# Ocreeb_MK_2__core__schematic.net
KiCad netlist of a schematic drawn in EAGLE
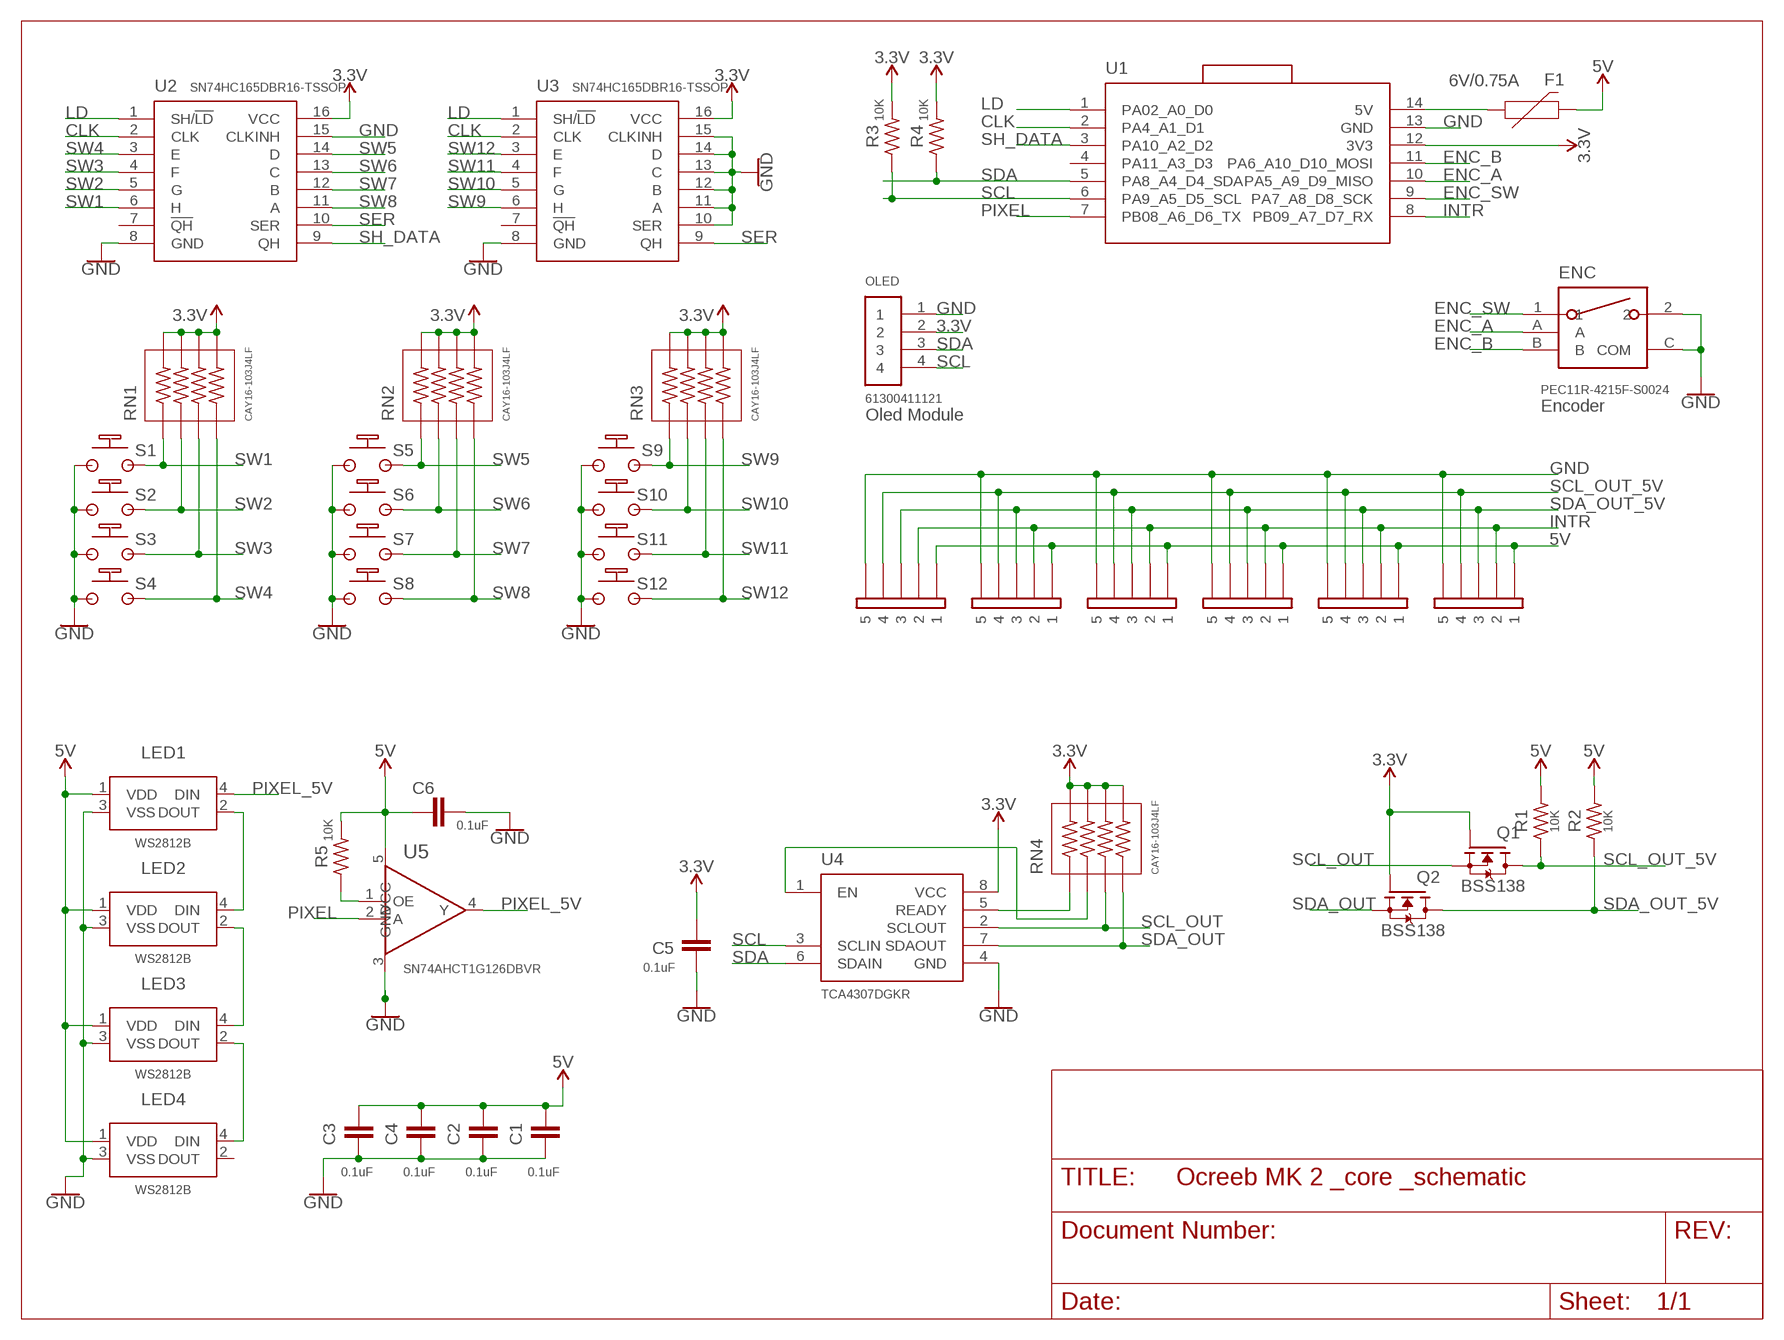
[diagram p0: schematic, sheet 1]

(export (version "E")
  (design (tool "Eeschema 10.0.6"))
  (components
    (comp (ref "C1")
      (value "0.1uF")
      (footprint "eagle-import:CAPC1608X85")
      (libsource (lib "eagle-import") (part "CCHIP-0603(1608-METRIC)_"))
    )
    (comp (ref "C2")
      (value "0.1uF")
      (footprint "eagle-import:CAPC1608X85")
      (libsource (lib "eagle-import") (part "CCHIP-0603(1608-METRIC)_"))
    )
    (comp (ref "C3")
      (value "0.1uF")
      (footprint "eagle-import:CAPC1608X85")
      (libsource (lib "eagle-import") (part "CCHIP-0603(1608-METRIC)_"))
    )
    (comp (ref "C4")
      (value "0.1uF")
      (footprint "eagle-import:CAPC1608X85")
      (libsource (lib "eagle-import") (part "CCHIP-0603(1608-METRIC)_"))
    )
    (comp (ref "C5")
      (value "0.1uF")
      (footprint "eagle-import:CAPC1608X85")
      (libsource (lib "eagle-import") (part "CCHIP-0603(1608-METRIC)_"))
    )
    (comp (ref "C6")
      (value "0.1uF")
      (footprint "eagle-import:CAPC1608X85")
      (libsource (lib "eagle-import") (part "CCHIP-0603(1608-METRIC)_"))
    )
    (comp (ref "ENC")
      (value "PEC11R-4215F-S0024")
      (footprint "eagle-import:PEC11R-4215F-S0024")
      (fields
        (field (name "DIGIKEY_PART_NUMBER") "PEC11R-4215F-S0024-ND")
        (field (name "MANUFACTURER") "Bourns Inc.")
        (field (name "CREATED_BY") "PCBLayout.com")
      )
      (libsource (lib "eagle-import") (part "PEC11R-4215F-S0024"))
    )
    (comp (ref "F1")
      (value "6V/0.75A")
      (footprint "eagle-import:1206")
      (libsource (lib "eagle-import") (part "PPTC_0.75A"))
    )
    (comp (ref "LED1")
      (value "WS2812B")
      (footprint "eagle-import:WS2812B")
      (fields (field (name "MANUFACTURER") "Worldsemi"))
      (libsource (lib "eagle-import") (part "WS2812B"))
    )
    (comp (ref "LED2")
      (value "WS2812B")
      (footprint "eagle-import:WS2812B")
      (fields (field (name "MANUFACTURER") "Worldsemi"))
      (libsource (lib "eagle-import") (part "WS2812B"))
    )
    (comp (ref "LED3")
      (value "WS2812B")
      (footprint "eagle-import:WS2812B")
      (fields (field (name "MANUFACTURER") "Worldsemi"))
      (libsource (lib "eagle-import") (part "WS2812B"))
    )
    (comp (ref "LED4")
      (value "WS2812B")
      (footprint "eagle-import:WS2812B")
      (fields (field (name "MANUFACTURER") "Worldsemi"))
      (libsource (lib "eagle-import") (part "WS2812B"))
    )
    (comp (ref "OLED")
      (value "61300411121")
      (footprint "eagle-import:61300411121")
      (fields
        (field (name "DIGI_KEY_PART_NUMBER") "732-5317-ND")
        (field (name "MANUFACTURER") "Wurth Electronics Inc.")
        (field (name "CREATED_BY") "PCBLayout.com")
      )
      (libsource (lib "eagle-import") (part "61300411121"))
    )
    (comp (ref "Q1")
      (value "BSS138")
      (footprint "eagle-import:SOT95P240X111-3N")
      (fields (field (name "MF") "onsemi"))
      (libsource (lib "eagle-import") (part "BSS138"))
    )
    (comp (ref "Q2")
      (value "BSS138")
      (footprint "eagle-import:SOT95P240X111-3N")
      (fields (field (name "MF") "onsemi"))
      (libsource (lib "eagle-import") (part "BSS138"))
    )
    (comp (ref "R1")
      (value "10K")
      (footprint "eagle-import:RESC1608X60")
      (libsource (lib "eagle-import") (part "R-USCHIP-0603(1608-METRIC)_"))
    )
    (comp (ref "R2")
      (value "10K")
      (footprint "eagle-import:RESC1608X60")
      (libsource (lib "eagle-import") (part "R-USCHIP-0603(1608-METRIC)_"))
    )
    (comp (ref "R3")
      (value "10K")
      (footprint "eagle-import:RESC1608X60")
      (libsource (lib "eagle-import") (part "R-USCHIP-0603(1608-METRIC)_"))
    )
    (comp (ref "R4")
      (value "10K")
      (footprint "eagle-import:RESC1608X60")
      (libsource (lib "eagle-import") (part "R-USCHIP-0603(1608-METRIC)_"))
    )
    (comp (ref "R5")
      (value "10K")
      (footprint "eagle-import:RESC1608X60")
      (libsource (lib "eagle-import") (part "R-USCHIP-0603(1608-METRIC)_"))
    )
    (comp (ref "RN1")
      (value "CAY16-103J4LF")
      (footprint "eagle-import:RESCAF80P320X160X60-8N")
      (fields (field (name "DIGIKEY_PART_NUMBER") "CAY16-103J4LFTR-ND") (field (name "MF") "Bourns"))
      (libsource (lib "eagle-import") (part "CAY16-103J4LF"))
    )
    (comp (ref "RN2")
      (value "CAY16-103J4LF")
      (footprint "eagle-import:RESCAF80P320X160X60-8N")
      (fields (field (name "DIGIKEY_PART_NUMBER") "CAY16-103J4LFTR-ND") (field (name "MF") "Bourns"))
      (libsource (lib "eagle-import") (part "CAY16-103J4LF"))
    )
    (comp (ref "RN3")
      (value "CAY16-103J4LF")
      (footprint "eagle-import:RESCAF80P320X160X60-8N")
      (fields (field (name "DIGIKEY_PART_NUMBER") "CAY16-103J4LFTR-ND") (field (name "MF") "Bourns"))
      (libsource (lib "eagle-import") (part "CAY16-103J4LF"))
    )
    (comp (ref "RN4")
      (value "CAY16-103J4LF")
      (footprint "eagle-import:RESCAF80P320X160X60-8N")
      (fields (field (name "DIGIKEY_PART_NUMBER") "CAY16-103J4LFTR-ND") (field (name "MF") "Bourns"))
      (libsource (lib "eagle-import") (part "CAY16-103J4LF"))
    )
    (comp (ref "S1")
      (value "MX1A-11NN")
      (footprint "eagle-import:CHERRY_MX1A-11NN_SWITCH")
      (fields (field (name "MF") "Cherry") (field (name "MP") "MX1A11NN"))
      (libsource (lib "eagle-import") (part "MX1A-11NN"))
    )
    (comp (ref "S2")
      (value "MX1A-11NN")
      (footprint "eagle-import:CHERRY_MX1A-11NN_SWITCH")
      (fields (field (name "MF") "Cherry") (field (name "MP") "MX1A11NN"))
      (libsource (lib "eagle-import") (part "MX1A-11NN"))
    )
    (comp (ref "S3")
      (value "MX1A-11NN")
      (footprint "eagle-import:CHERRY_MX1A-11NN_SWITCH")
      (fields (field (name "MF") "Cherry") (field (name "MP") "MX1A11NN"))
      (libsource (lib "eagle-import") (part "MX1A-11NN"))
    )
    (comp (ref "S4")
      (value "MX1A-11NN")
      (footprint "eagle-import:CHERRY_MX1A-11NN_SWITCH")
      (fields (field (name "MF") "Cherry") (field (name "MP") "MX1A11NN"))
      (libsource (lib "eagle-import") (part "MX1A-11NN"))
    )
    (comp (ref "S5")
      (value "MX1A-11NN")
      (footprint "eagle-import:CHERRY_MX1A-11NN_SWITCH")
      (fields (field (name "MF") "Cherry") (field (name "MP") "MX1A11NN"))
      (libsource (lib "eagle-import") (part "MX1A-11NN"))
    )
    (comp (ref "S6")
      (value "MX1A-11NN")
      (footprint "eagle-import:CHERRY_MX1A-11NN_SWITCH")
      (fields (field (name "MF") "Cherry") (field (name "MP") "MX1A11NN"))
      (libsource (lib "eagle-import") (part "MX1A-11NN"))
    )
    (comp (ref "S7")
      (value "MX1A-11NN")
      (footprint "eagle-import:CHERRY_MX1A-11NN_SWITCH")
      (fields (field (name "MF") "Cherry") (field (name "MP") "MX1A11NN"))
      (libsource (lib "eagle-import") (part "MX1A-11NN"))
    )
    (comp (ref "S8")
      (value "MX1A-11NN")
      (footprint "eagle-import:CHERRY_MX1A-11NN_SWITCH")
      (fields (field (name "MF") "Cherry") (field (name "MP") "MX1A11NN"))
      (libsource (lib "eagle-import") (part "MX1A-11NN"))
    )
    (comp (ref "S9")
      (value "MX1A-11NN")
      (footprint "eagle-import:CHERRY_MX1A-11NN_SWITCH")
      (fields (field (name "MF") "Cherry") (field (name "MP") "MX1A11NN"))
      (libsource (lib "eagle-import") (part "MX1A-11NN"))
    )
    (comp (ref "S10")
      (value "MX1A-11NN")
      (footprint "eagle-import:CHERRY_MX1A-11NN_SWITCH")
      (fields (field (name "MF") "Cherry") (field (name "MP") "MX1A11NN"))
      (libsource (lib "eagle-import") (part "MX1A-11NN"))
    )
    (comp (ref "S11")
      (value "MX1A-11NN")
      (footprint "eagle-import:CHERRY_MX1A-11NN_SWITCH")
      (fields (field (name "MF") "Cherry") (field (name "MP") "MX1A11NN"))
      (libsource (lib "eagle-import") (part "MX1A-11NN"))
    )
    (comp (ref "S12")
      (value "MX1A-11NN")
      (footprint "eagle-import:CHERRY_MX1A-11NN_SWITCH")
      (fields (field (name "MF") "Cherry") (field (name "MP") "MX1A11NN"))
      (libsource (lib "eagle-import") (part "MX1A-11NN"))
    )
    (comp (ref "U$1")
      (value "5PIN_EDGE")
      (footprint "eagle-import:5_POGO_EDGE")
      (libsource (lib "eagle-import") (part "5PIN_EDGE"))
    )
    (comp (ref "U$2")
      (value "5PIN_EDGE")
      (footprint "eagle-import:5_POGO_EDGE")
      (libsource (lib "eagle-import") (part "5PIN_EDGE"))
    )
    (comp (ref "U$3")
      (value "5PIN_EDGE")
      (footprint "eagle-import:5_POGO_EDGE")
      (libsource (lib "eagle-import") (part "5PIN_EDGE"))
    )
    (comp (ref "U$4")
      (value "5PIN_EDGE")
      (footprint "eagle-import:5_POGO_EDGE")
      (libsource (lib "eagle-import") (part "5PIN_EDGE"))
    )
    (comp (ref "U$5")
      (value "5PIN_EDGE")
      (footprint "eagle-import:5_POGO_EDGE")
      (libsource (lib "eagle-import") (part "5PIN_EDGE"))
    )
    (comp (ref "U$6")
      (value "5PIN_EDGE")
      (footprint "eagle-import:5_POGO_EDGE")
      (libsource (lib "eagle-import") (part "5PIN_EDGE"))
    )
    (comp (ref "U1")
      (value "MOUDLE-SEEEDUINO-XIAO-SMD")
      (footprint "eagle-import:MOUDLE14P-SMD-2.54-21X17.8MM")
      (libsource (lib "eagle-import") (part "MOUDLE-SEEEDUINO-XIAO-SMD"))
    )
    (comp (ref "U2")
      (value "SN74HC165DBR16-TSSOP")
      (footprint "eagle-import:SOP65P640X120-16N")
      (libsource (lib "eagle-import") (part "SN74HC165DBR16-TSSOP"))
    )
    (comp (ref "U3")
      (value "SN74HC165DBR16-TSSOP")
      (footprint "eagle-import:SOP65P640X120-16N")
      (libsource (lib "eagle-import") (part "SN74HC165DBR16-TSSOP"))
    )
    (comp (ref "U4")
      (value "TCA4307DGKR")
      (footprint "eagle-import:SOP65P490X110-8N")
      (fields (field (name "MF") "Texas Instruments"))
      (libsource (lib "eagle-import") (part "TCA4307DGKR"))
    )
    (comp (ref "U5")
      (value "SN74AHCT1G126DBVR")
      (footprint "eagle-import:SOT95P280X145-5N")
      (fields (field (name "DIGIKEY_PART_NUMBER") "296-4710-2-ND") (field (name "MF") "Texas Instruments"))
      (libsource (lib "eagle-import") (part "SN74AHCT1G126DBVR"))
    )
  )
  (nets
    (net (code "1") (name "/CLK") (class "Default")
      (node (ref "U1") (pin "2") (pinfunction "PA4_A1_D1_2") (pintype "bidirectional"))
      (node (ref "U2") (pin "2") (pinfunction "CLK_2") (pintype "input"))
      (node (ref "U3") (pin "2") (pinfunction "CLK_2") (pintype "input"))
    )
    (net (code "2") (name "/ENC_A") (class "Default")
      (node (ref "ENC") (pin "A") (pinfunction "A_A") (pintype "passive"))
      (node (ref "U1") (pin "10") (pinfunction "PA5_A9_D9_MISO_10") (pintype "bidirectional"))
    )
    (net (code "3") (name "/ENC_B") (class "Default")
      (node (ref "ENC") (pin "B") (pinfunction "B_B") (pintype "passive"))
      (node (ref "U1") (pin "11") (pinfunction "PA6_A10_D10_MOSI_11") (pintype "bidirectional"))
    )
    (net (code "4") (name "/ENC_SW") (class "Default")
      (node (ref "ENC") (pin "1") (pinfunction "1_1") (pintype "passive"))
      (node (ref "U1") (pin "9") (pinfunction "PA7_A8_D8_SCK_9") (pintype "bidirectional"))
    )
    (net (code "5") (name "/INTR") (class "Default")
      (node (ref "U$1") (pin "2") (pinfunction "2_2") (pintype "bidirectional"))
      (node (ref "U$2") (pin "2") (pinfunction "2_2") (pintype "bidirectional"))
      (node (ref "U$3") (pin "2") (pinfunction "2_2") (pintype "bidirectional"))
      (node (ref "U$4") (pin "2") (pinfunction "2_2") (pintype "bidirectional"))
      (node (ref "U$5") (pin "2") (pinfunction "2_2") (pintype "bidirectional"))
      (node (ref "U$6") (pin "2") (pinfunction "2_2") (pintype "bidirectional"))
      (node (ref "U1") (pin "8") (pinfunction "PB09_A7_D7_RX_8") (pintype "bidirectional"))
    )
    (net (code "6") (name "/LD") (class "Default")
      (node (ref "U1") (pin "1") (pinfunction "PA02_A0_D0_1") (pintype "bidirectional"))
      (node (ref "U2") (pin "1") (pinfunction "SH/~{LD}_1") (pintype "input"))
      (node (ref "U3") (pin "1") (pinfunction "SH/~{LD}_1") (pintype "input"))
    )
    (net (code "7") (name "/PIXEL") (class "Default")
      (node (ref "U1") (pin "7") (pinfunction "PB08_A6_D6_TX_7") (pintype "bidirectional"))
      (node (ref "U5") (pin "2") (pinfunction "A_2") (pintype "input"))
    )
    (net (code "8") (name "/PIXEL_5V") (class "Default")
      (node (ref "LED1") (pin "4") (pinfunction "DIN_4") (pintype "input"))
      (node (ref "U5") (pin "4") (pinfunction "Y_4") (pintype "output"))
    )
    (net (code "9") (name "/SCL") (class "Default")
      (node (ref "OLED") (pin "4") (pinfunction "4_4") (pintype "passive"))
      (node (ref "R3") (pin "1") (pinfunction "1_1") (pintype "passive"))
      (node (ref "U1") (pin "6") (pinfunction "PA9_A5_D5_SCL_6") (pintype "bidirectional"))
      (node (ref "U4") (pin "3") (pinfunction "SCLIN_3") (pintype "input"))
    )
    (net (code "10") (name "/SCL_OUT") (class "Default")
      (node (ref "Q1") (pin "2") (pinfunction "S_2") (pintype "passive"))
      (node (ref "RN4") (pin "3") (pinfunction "3_3") (pintype "passive"))
      (node (ref "U4") (pin "2") (pinfunction "SCLOUT_2") (pintype "output"))
    )
    (net (code "11") (name "/SCL_OUT_5V") (class "Default")
      (node (ref "Q1") (pin "3") (pinfunction "D_3") (pintype "passive"))
      (node (ref "R1") (pin "1") (pinfunction "1_1") (pintype "passive"))
      (node (ref "U$1") (pin "4") (pinfunction "4_4") (pintype "bidirectional"))
      (node (ref "U$2") (pin "4") (pinfunction "4_4") (pintype "bidirectional"))
      (node (ref "U$3") (pin "4") (pinfunction "4_4") (pintype "bidirectional"))
      (node (ref "U$4") (pin "4") (pinfunction "4_4") (pintype "bidirectional"))
      (node (ref "U$5") (pin "4") (pinfunction "4_4") (pintype "bidirectional"))
      (node (ref "U$6") (pin "4") (pinfunction "4_4") (pintype "bidirectional"))
    )
    (net (code "12") (name "/SDA") (class "Default")
      (node (ref "OLED") (pin "3") (pinfunction "3_3") (pintype "passive"))
      (node (ref "R4") (pin "1") (pinfunction "1_1") (pintype "passive"))
      (node (ref "U1") (pin "5") (pinfunction "PA8_A4_D4_SDA_5") (pintype "bidirectional"))
      (node (ref "U4") (pin "6") (pinfunction "SDAIN_6") (pintype "input"))
    )
    (net (code "13") (name "/SDA_OUT") (class "Default")
      (node (ref "Q2") (pin "2") (pinfunction "S_2") (pintype "passive"))
      (node (ref "RN4") (pin "4") (pinfunction "4_4") (pintype "passive"))
      (node (ref "U4") (pin "7") (pinfunction "SDAOUT_7") (pintype "output"))
    )
    (net (code "14") (name "/SDA_OUT_5V") (class "Default")
      (node (ref "Q2") (pin "3") (pinfunction "D_3") (pintype "passive"))
      (node (ref "R2") (pin "1") (pinfunction "1_1") (pintype "passive"))
      (node (ref "U$1") (pin "3") (pinfunction "3_3") (pintype "bidirectional"))
      (node (ref "U$2") (pin "3") (pinfunction "3_3") (pintype "bidirectional"))
      (node (ref "U$3") (pin "3") (pinfunction "3_3") (pintype "bidirectional"))
      (node (ref "U$4") (pin "3") (pinfunction "3_3") (pintype "bidirectional"))
      (node (ref "U$5") (pin "3") (pinfunction "3_3") (pintype "bidirectional"))
      (node (ref "U$6") (pin "3") (pinfunction "3_3") (pintype "bidirectional"))
    )
    (net (code "15") (name "/SER") (class "Default")
      (node (ref "U2") (pin "10") (pinfunction "SER_10") (pintype "input"))
      (node (ref "U3") (pin "9") (pinfunction "QH_9") (pintype "output"))
    )
    (net (code "16") (name "/SH_DATA") (class "Default")
      (node (ref "U1") (pin "3") (pinfunction "PA10_A2_D2_3") (pintype "bidirectional"))
      (node (ref "U2") (pin "9") (pinfunction "QH_9") (pintype "output"))
    )
    (net (code "17") (name "/SW1") (class "Default")
      (node (ref "RN1") (pin "1") (pinfunction "1_1") (pintype "passive"))
      (node (ref "S1") (pin "2") (pinfunction "2_2") (pintype "passive"))
      (node (ref "S1") (pin "2_ALT") (pinfunction "2_2_ALT") (pintype "passive"))
      (node (ref "U2") (pin "6") (pinfunction "H_6") (pintype "input"))
    )
    (net (code "18") (name "/SW2") (class "Default")
      (node (ref "RN1") (pin "2") (pinfunction "2_2") (pintype "passive"))
      (node (ref "S2") (pin "2") (pinfunction "2_2") (pintype "passive"))
      (node (ref "S2") (pin "2_ALT") (pinfunction "2_2_ALT") (pintype "passive"))
      (node (ref "U2") (pin "5") (pinfunction "G_5") (pintype "input"))
    )
    (net (code "19") (name "/SW3") (class "Default")
      (node (ref "RN1") (pin "3") (pinfunction "3_3") (pintype "passive"))
      (node (ref "S3") (pin "2") (pinfunction "2_2") (pintype "passive"))
      (node (ref "S3") (pin "2_ALT") (pinfunction "2_2_ALT") (pintype "passive"))
      (node (ref "U2") (pin "4") (pinfunction "F_4") (pintype "input"))
    )
    (net (code "20") (name "/SW4") (class "Default")
      (node (ref "RN1") (pin "4") (pinfunction "4_4") (pintype "passive"))
      (node (ref "S4") (pin "2") (pinfunction "2_2") (pintype "passive"))
      (node (ref "S4") (pin "2_ALT") (pinfunction "2_2_ALT") (pintype "passive"))
      (node (ref "U2") (pin "3") (pinfunction "E_3") (pintype "input"))
    )
    (net (code "21") (name "/SW5") (class "Default")
      (node (ref "RN2") (pin "1") (pinfunction "1_1") (pintype "passive"))
      (node (ref "S5") (pin "2") (pinfunction "2_2") (pintype "passive"))
      (node (ref "S5") (pin "2_ALT") (pinfunction "2_2_ALT") (pintype "passive"))
      (node (ref "U2") (pin "14") (pinfunction "D_14") (pintype "input"))
    )
    (net (code "22") (name "/SW6") (class "Default")
      (node (ref "RN2") (pin "2") (pinfunction "2_2") (pintype "passive"))
      (node (ref "S6") (pin "2") (pinfunction "2_2") (pintype "passive"))
      (node (ref "S6") (pin "2_ALT") (pinfunction "2_2_ALT") (pintype "passive"))
      (node (ref "U2") (pin "13") (pinfunction "C_13") (pintype "input"))
    )
    (net (code "23") (name "/SW7") (class "Default")
      (node (ref "RN2") (pin "3") (pinfunction "3_3") (pintype "passive"))
      (node (ref "S7") (pin "2") (pinfunction "2_2") (pintype "passive"))
      (node (ref "S7") (pin "2_ALT") (pinfunction "2_2_ALT") (pintype "passive"))
      (node (ref "U2") (pin "12") (pinfunction "B_12") (pintype "input"))
    )
    (net (code "24") (name "/SW8") (class "Default")
      (node (ref "RN2") (pin "4") (pinfunction "4_4") (pintype "passive"))
      (node (ref "S8") (pin "2") (pinfunction "2_2") (pintype "passive"))
      (node (ref "S8") (pin "2_ALT") (pinfunction "2_2_ALT") (pintype "passive"))
      (node (ref "U2") (pin "11") (pinfunction "A_11") (pintype "input"))
    )
    (net (code "25") (name "/SW9") (class "Default")
      (node (ref "RN3") (pin "1") (pinfunction "1_1") (pintype "passive"))
      (node (ref "S9") (pin "2") (pinfunction "2_2") (pintype "passive"))
      (node (ref "S9") (pin "2_ALT") (pinfunction "2_2_ALT") (pintype "passive"))
      (node (ref "U3") (pin "6") (pinfunction "H_6") (pintype "input"))
    )
    (net (code "26") (name "/SW10") (class "Default")
      (node (ref "RN3") (pin "2") (pinfunction "2_2") (pintype "passive"))
      (node (ref "S10") (pin "2") (pinfunction "2_2") (pintype "passive"))
      (node (ref "S10") (pin "2_ALT") (pinfunction "2_2_ALT") (pintype "passive"))
      (node (ref "U3") (pin "5") (pinfunction "G_5") (pintype "input"))
    )
    (net (code "27") (name "/SW11") (class "Default")
      (node (ref "RN3") (pin "3") (pinfunction "3_3") (pintype "passive"))
      (node (ref "S11") (pin "2") (pinfunction "2_2") (pintype "passive"))
      (node (ref "S11") (pin "2_ALT") (pinfunction "2_2_ALT") (pintype "passive"))
      (node (ref "U3") (pin "4") (pinfunction "F_4") (pintype "input"))
    )
    (net (code "28") (name "/SW12") (class "Default")
      (node (ref "RN3") (pin "4") (pinfunction "4_4") (pintype "passive"))
      (node (ref "S12") (pin "2") (pinfunction "2_2") (pintype "passive"))
      (node (ref "S12") (pin "2_ALT") (pinfunction "2_2_ALT") (pintype "passive"))
      (node (ref "U3") (pin "3") (pinfunction "E_3") (pintype "input"))
    )
    (net (code "29") (name "3.3V") (class "Default")
      (node (ref "C5") (pin "2") (pinfunction "2_2") (pintype "passive"))
      (node (ref "OLED") (pin "2") (pinfunction "2_2") (pintype "passive"))
      (node (ref "Q1") (pin "1") (pinfunction "G_1") (pintype "passive"))
      (node (ref "Q2") (pin "1") (pinfunction "G_1") (pintype "passive"))
      (node (ref "R3") (pin "2") (pinfunction "2_2") (pintype "passive"))
      (node (ref "R4") (pin "2") (pinfunction "2_2") (pintype "passive"))
      (node (ref "RN1") (pin "5") (pinfunction "5_5") (pintype "passive"))
      (node (ref "RN1") (pin "6") (pinfunction "6_6") (pintype "passive"))
      (node (ref "RN1") (pin "7") (pinfunction "7_7") (pintype "passive"))
      (node (ref "RN1") (pin "8") (pinfunction "8_8") (pintype "passive"))
      (node (ref "RN2") (pin "5") (pinfunction "5_5") (pintype "passive"))
      (node (ref "RN2") (pin "6") (pinfunction "6_6") (pintype "passive"))
      (node (ref "RN2") (pin "7") (pinfunction "7_7") (pintype "passive"))
      (node (ref "RN2") (pin "8") (pinfunction "8_8") (pintype "passive"))
      (node (ref "RN3") (pin "5") (pinfunction "5_5") (pintype "passive"))
      (node (ref "RN3") (pin "6") (pinfunction "6_6") (pintype "passive"))
      (node (ref "RN3") (pin "7") (pinfunction "7_7") (pintype "passive"))
      (node (ref "RN3") (pin "8") (pinfunction "8_8") (pintype "passive"))
      (node (ref "RN4") (pin "5") (pinfunction "5_5") (pintype "passive"))
      (node (ref "RN4") (pin "6") (pinfunction "6_6") (pintype "passive"))
      (node (ref "RN4") (pin "7") (pinfunction "7_7") (pintype "passive"))
      (node (ref "RN4") (pin "8") (pinfunction "8_8") (pintype "passive"))
      (node (ref "U1") (pin "12") (pinfunction "3V3_12") (pintype "bidirectional"))
      (node (ref "U2") (pin "16") (pinfunction "VCC_16") (pintype "power_in"))
      (node (ref "U3") (pin "16") (pinfunction "VCC_16") (pintype "power_in"))
      (node (ref "U4") (pin "8") (pinfunction "VCC_8") (pintype "power_in"))
    )
    (net (code "30") (name "5V") (class "Default")
      (node (ref "C1") (pin "2") (pinfunction "2_2") (pintype "passive"))
      (node (ref "C2") (pin "2") (pinfunction "2_2") (pintype "passive"))
      (node (ref "C3") (pin "2") (pinfunction "2_2") (pintype "passive"))
      (node (ref "C4") (pin "2") (pinfunction "2_2") (pintype "passive"))
      (node (ref "C6") (pin "2") (pinfunction "2_2") (pintype "passive"))
      (node (ref "F1") (pin "2") (pinfunction "2_2") (pintype "bidirectional"))
      (node (ref "LED1") (pin "1") (pinfunction "VDD_1") (pintype "power_in"))
      (node (ref "LED2") (pin "1") (pinfunction "VDD_1") (pintype "power_in"))
      (node (ref "LED3") (pin "1") (pinfunction "VDD_1") (pintype "power_in"))
      (node (ref "LED4") (pin "1") (pinfunction "VDD_1") (pintype "power_in"))
      (node (ref "R1") (pin "2") (pinfunction "2_2") (pintype "passive"))
      (node (ref "R2") (pin "2") (pinfunction "2_2") (pintype "passive"))
      (node (ref "R5") (pin "2") (pinfunction "2_2") (pintype "passive"))
      (node (ref "U$1") (pin "1") (pinfunction "1_1") (pintype "bidirectional"))
      (node (ref "U$2") (pin "1") (pinfunction "1_1") (pintype "bidirectional"))
      (node (ref "U$3") (pin "1") (pinfunction "1_1") (pintype "bidirectional"))
      (node (ref "U$4") (pin "1") (pinfunction "1_1") (pintype "bidirectional"))
      (node (ref "U$5") (pin "1") (pinfunction "1_1") (pintype "bidirectional"))
      (node (ref "U$6") (pin "1") (pinfunction "1_1") (pintype "bidirectional"))
      (node (ref "U5") (pin "5") (pinfunction "VCC_5") (pintype "power_in"))
    )
    (net (code "31") (name "GND") (class "Default")
      (node (ref "C1") (pin "1") (pinfunction "1_1") (pintype "passive"))
      (node (ref "C2") (pin "1") (pinfunction "1_1") (pintype "passive"))
      (node (ref "C3") (pin "1") (pinfunction "1_1") (pintype "passive"))
      (node (ref "C4") (pin "1") (pinfunction "1_1") (pintype "passive"))
      (node (ref "C5") (pin "1") (pinfunction "1_1") (pintype "passive"))
      (node (ref "C6") (pin "1") (pinfunction "1_1") (pintype "passive"))
      (node (ref "ENC") (pin "2") (pinfunction "2_2") (pintype "passive"))
      (node (ref "ENC") (pin "C") (pinfunction "COM_C") (pintype "passive"))
      (node (ref "LED1") (pin "3") (pinfunction "VSS_3") (pintype "power_in"))
      (node (ref "LED2") (pin "3") (pinfunction "VSS_3") (pintype "power_in"))
      (node (ref "LED3") (pin "3") (pinfunction "VSS_3") (pintype "power_in"))
      (node (ref "LED4") (pin "3") (pinfunction "VSS_3") (pintype "power_in"))
      (node (ref "OLED") (pin "1") (pinfunction "1_1") (pintype "passive"))
      (node (ref "S1") (pin "1") (pinfunction "1_1") (pintype "passive"))
      (node (ref "S1") (pin "1_ALT") (pinfunction "1_1_ALT") (pintype "passive"))
      (node (ref "S10") (pin "1") (pinfunction "1_1") (pintype "passive"))
      (node (ref "S10") (pin "1_ALT") (pinfunction "1_1_ALT") (pintype "passive"))
      (node (ref "S11") (pin "1") (pinfunction "1_1") (pintype "passive"))
      (node (ref "S11") (pin "1_ALT") (pinfunction "1_1_ALT") (pintype "passive"))
      (node (ref "S12") (pin "1") (pinfunction "1_1") (pintype "passive"))
      (node (ref "S12") (pin "1_ALT") (pinfunction "1_1_ALT") (pintype "passive"))
      (node (ref "S2") (pin "1") (pinfunction "1_1") (pintype "passive"))
      (node (ref "S2") (pin "1_ALT") (pinfunction "1_1_ALT") (pintype "passive"))
      (node (ref "S3") (pin "1") (pinfunction "1_1") (pintype "passive"))
      (node (ref "S3") (pin "1_ALT") (pinfunction "1_1_ALT") (pintype "passive"))
      (node (ref "S4") (pin "1") (pinfunction "1_1") (pintype "passive"))
      (node (ref "S4") (pin "1_ALT") (pinfunction "1_1_ALT") (pintype "passive"))
      (node (ref "S5") (pin "1") (pinfunction "1_1") (pintype "passive"))
      (node (ref "S5") (pin "1_ALT") (pinfunction "1_1_ALT") (pintype "passive"))
      (node (ref "S6") (pin "1") (pinfunction "1_1") (pintype "passive"))
      (node (ref "S6") (pin "1_ALT") (pinfunction "1_1_ALT") (pintype "passive"))
      (node (ref "S7") (pin "1") (pinfunction "1_1") (pintype "passive"))
      (node (ref "S7") (pin "1_ALT") (pinfunction "1_1_ALT") (pintype "passive"))
      (node (ref "S8") (pin "1") (pinfunction "1_1") (pintype "passive"))
      (node (ref "S8") (pin "1_ALT") (pinfunction "1_1_ALT") (pintype "passive"))
      (node (ref "S9") (pin "1") (pinfunction "1_1") (pintype "passive"))
      (node (ref "S9") (pin "1_ALT") (pinfunction "1_1_ALT") (pintype "passive"))
      (node (ref "U$1") (pin "5") (pinfunction "5_5") (pintype "bidirectional"))
      (node (ref "U$2") (pin "5") (pinfunction "5_5") (pintype "bidirectional"))
      (node (ref "U$3") (pin "5") (pinfunction "5_5") (pintype "bidirectional"))
      (node (ref "U$4") (pin "5") (pinfunction "5_5") (pintype "bidirectional"))
      (node (ref "U$5") (pin "5") (pinfunction "5_5") (pintype "bidirectional"))
      (node (ref "U$6") (pin "5") (pinfunction "5_5") (pintype "bidirectional"))
      (node (ref "U1") (pin "13") (pinfunction "GND_13") (pintype "bidirectional"))
      (node (ref "U2") (pin "15") (pinfunction "CLKINH_15") (pintype "input"))
      (node (ref "U2") (pin "8") (pinfunction "GND_8") (pintype "power_in"))
      (node (ref "U3") (pin "10") (pinfunction "SER_10") (pintype "input"))
      (node (ref "U3") (pin "11") (pinfunction "A_11") (pintype "input"))
      (node (ref "U3") (pin "12") (pinfunction "B_12") (pintype "input"))
      (node (ref "U3") (pin "13") (pinfunction "C_13") (pintype "input"))
      (node (ref "U3") (pin "14") (pinfunction "D_14") (pintype "input"))
      (node (ref "U3") (pin "15") (pinfunction "CLKINH_15") (pintype "input"))
      (node (ref "U3") (pin "8") (pinfunction "GND_8") (pintype "power_in"))
      (node (ref "U4") (pin "4") (pinfunction "GND_4") (pintype "power_in"))
      (node (ref "U5") (pin "3") (pinfunction "GND_3") (pintype "power_in"))
    )
    (net (code "32") (name "Net-(LED1-DOUT)") (class "Default")
      (node (ref "LED1") (pin "2") (pinfunction "DOUT_2") (pintype "output"))
      (node (ref "LED2") (pin "4") (pinfunction "DIN_4") (pintype "input"))
    )
    (net (code "33") (name "Net-(LED2-DOUT)") (class "Default")
      (node (ref "LED2") (pin "2") (pinfunction "DOUT_2") (pintype "output"))
      (node (ref "LED3") (pin "4") (pinfunction "DIN_4") (pintype "input"))
    )
    (net (code "34") (name "Net-(LED3-DOUT)") (class "Default")
      (node (ref "LED3") (pin "2") (pinfunction "DOUT_2") (pintype "output"))
      (node (ref "LED4") (pin "4") (pinfunction "DIN_4") (pintype "input"))
    )
    (net (code "35") (name "Net-(U1-5V)") (class "Default")
      (node (ref "F1") (pin "1") (pinfunction "1_1") (pintype "bidirectional"))
      (node (ref "U1") (pin "14") (pinfunction "5V_14") (pintype "bidirectional"))
    )
    (net (code "36") (name "Net-(U4-EN)") (class "Default")
      (node (ref "RN4") (pin "2") (pinfunction "2_2") (pintype "passive"))
      (node (ref "U4") (pin "1") (pinfunction "EN_1") (pintype "input"))
    )
    (net (code "37") (name "Net-(U4-READY)") (class "Default")
      (node (ref "RN4") (pin "1") (pinfunction "1_1") (pintype "passive"))
      (node (ref "U4") (pin "5") (pinfunction "READY_5") (pintype "output"))
    )
    (net (code "38") (name "Net-(U5-OE)") (class "Default")
      (node (ref "R5") (pin "1") (pinfunction "1_1") (pintype "passive"))
      (node (ref "U5") (pin "1") (pinfunction "OE_1") (pintype "input"))
    )
    (net (code "39") (name "unconnected-(LED4-DOUT-Pad2)") (class "Default")
      (node (ref "LED4") (pin "2") (pinfunction "DOUT_2") (pintype "output"))
    )
    (net (code "40") (name "unconnected-(U1-PA11_A3_D3-Pad4)") (class "Default")
      (node (ref "U1") (pin "4") (pinfunction "PA11_A3_D3_4") (pintype "bidirectional"))
    )
    (net (code "41") (name "unconnected-(U2-~{QH}-Pad7)") (class "Default")
      (node (ref "U2") (pin "7") (pinfunction "~{QH}_7") (pintype "output"))
    )
    (net (code "42") (name "unconnected-(U3-~{QH}-Pad7)") (class "Default")
      (node (ref "U3") (pin "7") (pinfunction "~{QH}_7") (pintype "output"))
    )
  )
)
